# ODGIRON-v1_0-F4x1-0410.net
KiCad netlist of a schematic drawn in EAGLE
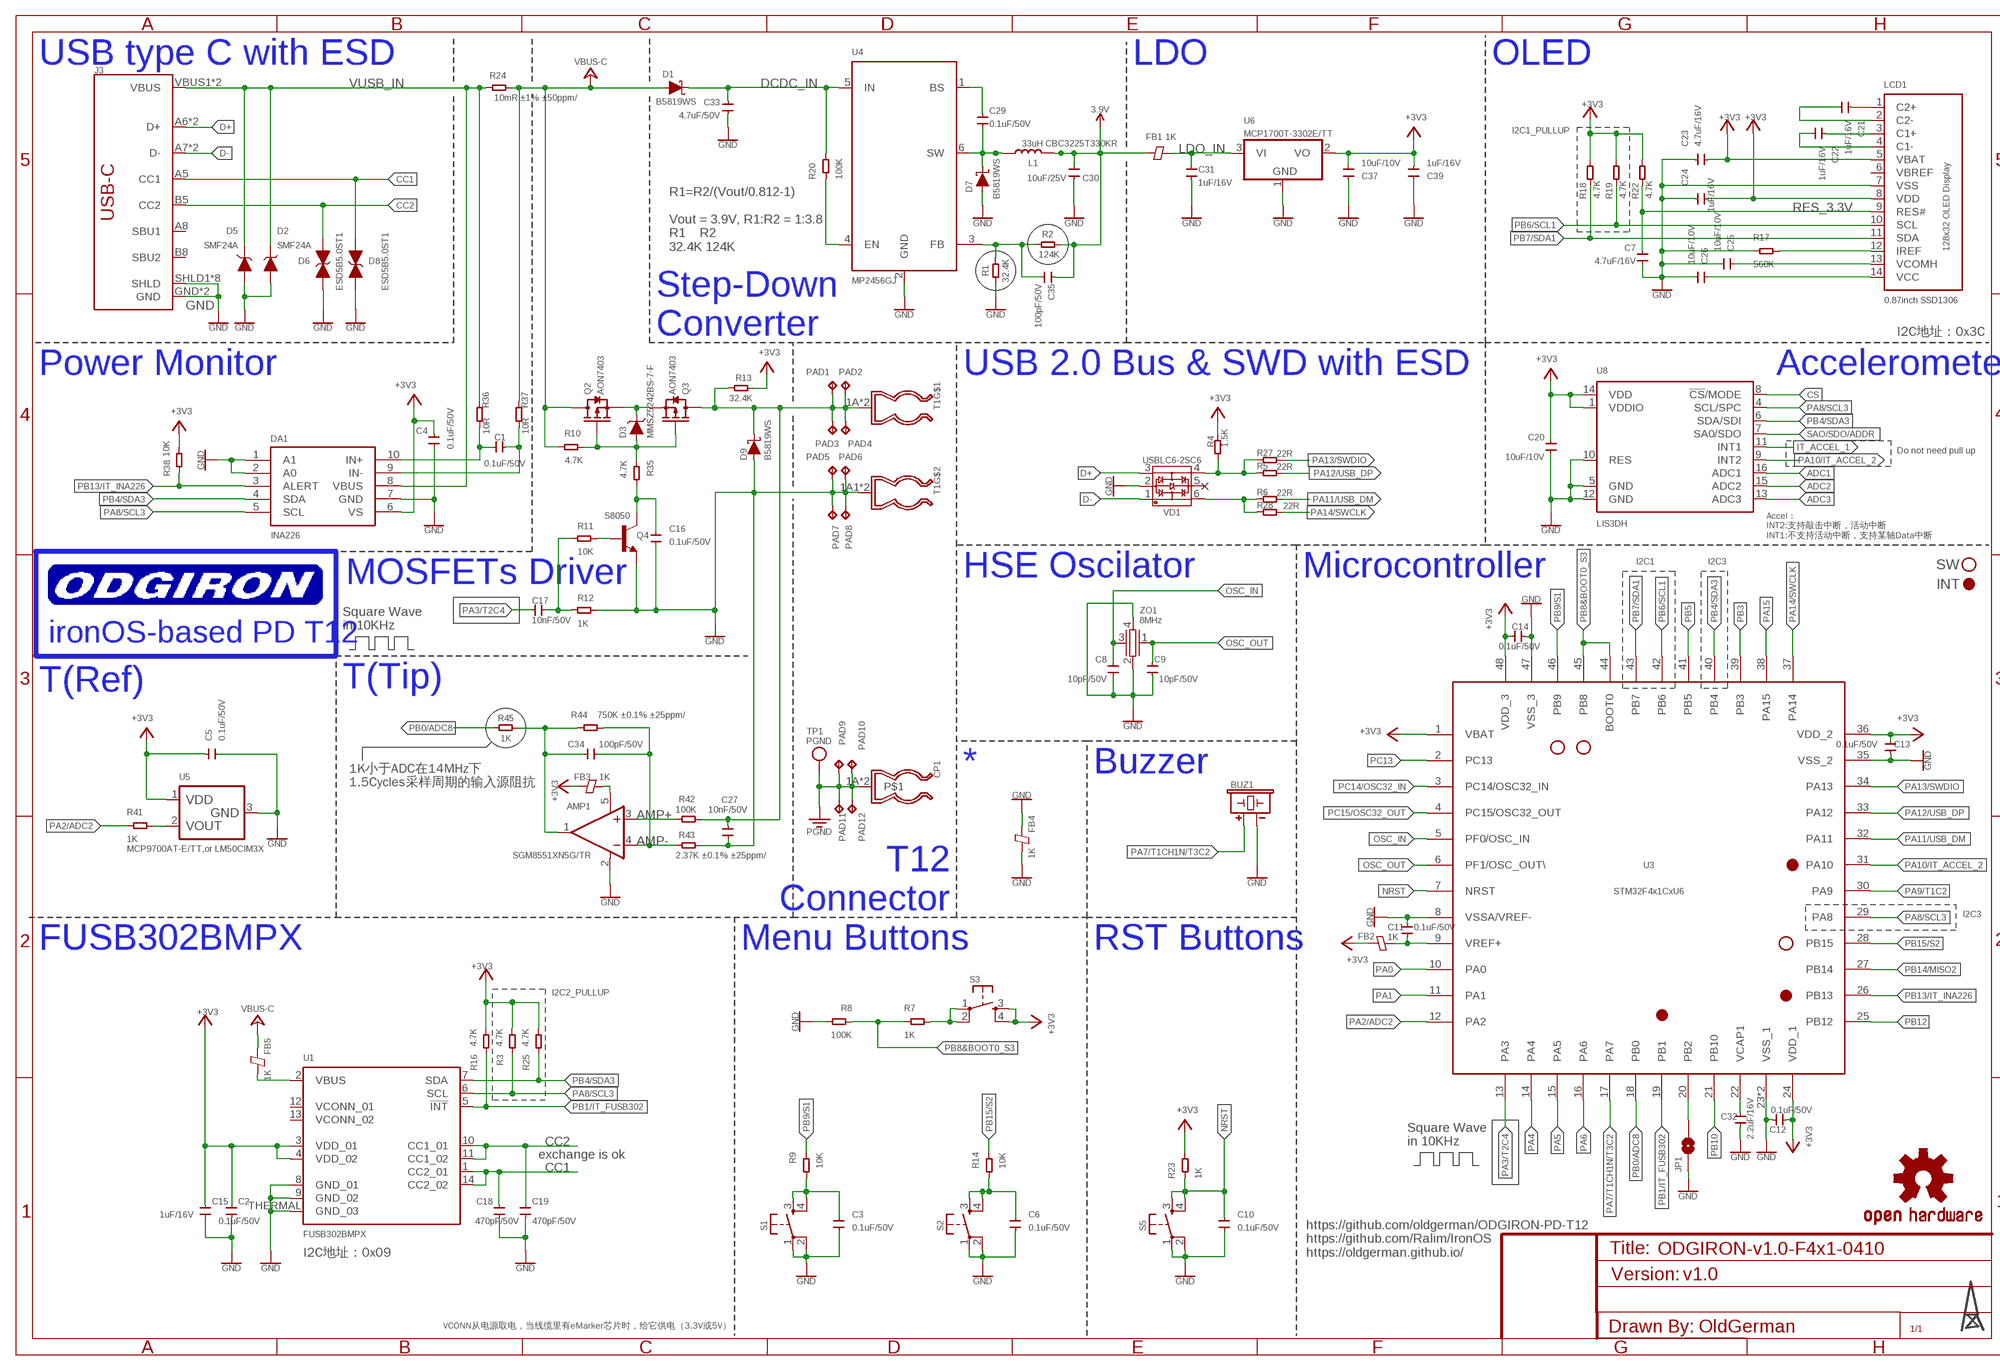
[diagram p0: schematic, sheet 1, part 1 of 2]
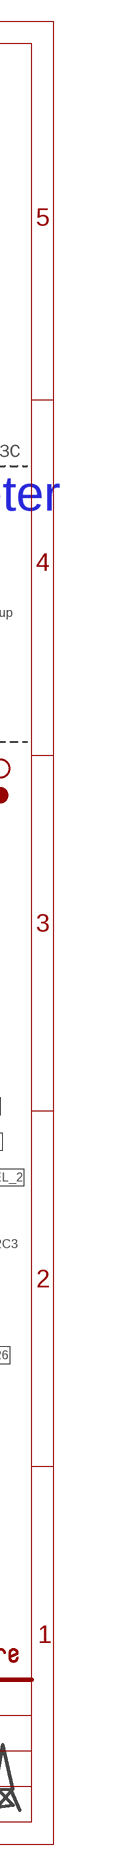
[diagram p1: schematic, sheet 1, part 2 of 2]

(export (version "E")
  (design (tool "Eeschema 10.0.6"))
  (components
    (comp (ref "AMP1")
      (value "SGM8551XN5G/TR")
      (footprint "eagle-import:SOT23-5")
      (fields (field (name "MPN") "OPA340NA/3KG4"))
      (libsource (lib "eagle-import") (part "AMP_SIMGLEN"))
    )
    (comp (ref "BUZ1")
      (value "BUZZERBUZZER_5020")
      (footprint "eagle-import:BUZZER_5020")
      (libsource (lib "eagle-import") (part "BUZZERBUZZER_5020"))
    )
    (comp (ref "C1")
      (value "0.1uF/50V")
      (footprint "eagle-import:C0603")
      (libsource (lib "eagle-import") (part "SEEED_CAP-0603"))
    )
    (comp (ref "C2")
      (value "0.1uF/50V")
      (footprint "eagle-import:C0603")
      (libsource (lib "eagle-import") (part "SEEED_CAP-0603"))
    )
    (comp (ref "C3")
      (value "0.1uF/50V")
      (footprint "eagle-import:C0603")
      (libsource (lib "eagle-import") (part "SEEED_CAP-0603"))
    )
    (comp (ref "C4")
      (value "0.1uF/50V")
      (footprint "eagle-import:C0603")
      (libsource (lib "eagle-import") (part "SEEED_CAP-0603"))
    )
    (comp (ref "C5")
      (value "0.1uF/50V")
      (footprint "eagle-import:C0603")
      (libsource (lib "eagle-import") (part "SEEED_CAP-0603"))
    )
    (comp (ref "C6")
      (value "0.1uF/50V")
      (footprint "eagle-import:C0603")
      (libsource (lib "eagle-import") (part "SEEED_CAP-0603"))
    )
    (comp (ref "C7")
      (value "4.7uF/16V")
      (footprint "eagle-import:C0603")
      (libsource (lib "eagle-import") (part "SEEED_CAP-0603"))
    )
    (comp (ref "C8")
      (value "10pF/50V")
      (footprint "eagle-import:C0603")
      (libsource (lib "eagle-import") (part "SEEED_CAP-0603"))
    )
    (comp (ref "C9")
      (value "10pF/50V")
      (footprint "eagle-import:C0603")
      (libsource (lib "eagle-import") (part "SEEED_CAP-0603"))
    )
    (comp (ref "C10")
      (value "0.1uF/50V")
      (footprint "eagle-import:C0603")
      (libsource (lib "eagle-import") (part "SEEED_CAP-0603"))
    )
    (comp (ref "C11")
      (value "0.1uF/50V")
      (footprint "eagle-import:C0603")
      (libsource (lib "eagle-import") (part "SEEED_CAP-0603"))
    )
    (comp (ref "C12")
      (value "0.1uF/50V")
      (footprint "eagle-import:C0603")
      (libsource (lib "eagle-import") (part "SEEED_CAP-0603"))
    )
    (comp (ref "C13")
      (value "0.1uF/50V")
      (footprint "eagle-import:C0603")
      (libsource (lib "eagle-import") (part "SEEED_CAP-0603"))
    )
    (comp (ref "C14")
      (value "0.1uF/50V")
      (footprint "eagle-import:C0603")
      (libsource (lib "eagle-import") (part "SEEED_CAP-0603"))
    )
    (comp (ref "C15")
      (value "1uF/16V")
      (footprint "eagle-import:C0603")
      (libsource (lib "eagle-import") (part "SEEED_CAP-0603"))
    )
    (comp (ref "C16")
      (value "0.1uF/50V")
      (footprint "eagle-import:C0603")
      (libsource (lib "eagle-import") (part "SEEED_CAP-0603"))
    )
    (comp (ref "C17")
      (value "10nF/50V")
      (footprint "eagle-import:C0603")
      (libsource (lib "eagle-import") (part "SEEED_CAP-0603"))
    )
    (comp (ref "C18")
      (value "470pF/50V")
      (footprint "eagle-import:C0603")
      (libsource (lib "eagle-import") (part "SEEED_CAP-0603"))
    )
    (comp (ref "C19")
      (value "470pF/50V")
      (footprint "eagle-import:C0603")
      (libsource (lib "eagle-import") (part "SEEED_CAP-0603"))
    )
    (comp (ref "C20")
      (value "10uF/10V")
      (footprint "eagle-import:C0603")
      (libsource (lib "eagle-import") (part "SEEED_CAP-0603"))
    )
    (comp (ref "C21")
      (value "1uF/16V")
      (footprint "eagle-import:C0603")
      (libsource (lib "eagle-import") (part "SEEED_CAP-0603"))
    )
    (comp (ref "C22")
      (value "1uF/16V")
      (footprint "eagle-import:C0603")
      (libsource (lib "eagle-import") (part "SEEED_CAP-0603"))
    )
    (comp (ref "C23")
      (value "4.7uF/16V")
      (footprint "eagle-import:C0603")
      (libsource (lib "eagle-import") (part "SEEED_CAP-0603"))
    )
    (comp (ref "C24")
      (value "1uF/16V")
      (footprint "eagle-import:C0603")
      (libsource (lib "eagle-import") (part "SEEED_CAP-0603"))
    )
    (comp (ref "C25")
      (value "10uF/10V")
      (footprint "eagle-import:C0603")
      (libsource (lib "eagle-import") (part "SEEED_CAP-0603"))
    )
    (comp (ref "C26")
      (value "10uF/10V")
      (footprint "eagle-import:C0603")
      (libsource (lib "eagle-import") (part "SEEED_CAP-0603"))
    )
    (comp (ref "C27")
      (value "10nF/50V")
      (footprint "eagle-import:C0603")
      (libsource (lib "eagle-import") (part "SEEED_CAP-0603"))
    )
    (comp (ref "C29")
      (value "0.1uF/50V")
      (footprint "eagle-import:C0603")
      (libsource (lib "eagle-import") (part "SEEED_CAP-0603"))
    )
    (comp (ref "C30")
      (value "10uF/25V")
      (footprint "eagle-import:C0805")
      (libsource (lib "eagle-import") (part "SEEED_CAP-0805"))
    )
    (comp (ref "C31")
      (value "1uF/16V")
      (footprint "eagle-import:C0603")
      (libsource (lib "eagle-import") (part "SEEED_CAP-0603"))
    )
    (comp (ref "C32")
      (value "2.2uF/16V")
      (footprint "eagle-import:C0603")
      (libsource (lib "eagle-import") (part "SEEED_CAP-0603"))
    )
    (comp (ref "C33")
      (value "4.7uF/50V")
      (footprint "eagle-import:C0805")
      (libsource (lib "eagle-import") (part "SEEED_CAP-0805"))
    )
    (comp (ref "C34")
      (value "100pF/50V")
      (footprint "eagle-import:C0603")
      (libsource (lib "eagle-import") (part "SEEED_CAP-0603"))
    )
    (comp (ref "C35")
      (value "100pF/50V")
      (footprint "eagle-import:C0603")
      (libsource (lib "eagle-import") (part "SEEED_CAP-0603"))
    )
    (comp (ref "C37")
      (value "10uF/10V")
      (footprint "eagle-import:C0603")
      (libsource (lib "eagle-import") (part "SEEED_CAP-0603"))
    )
    (comp (ref "C39")
      (value "1uF/16V")
      (footprint "eagle-import:C0603")
      (libsource (lib "eagle-import") (part "SEEED_CAP-0603"))
    )
    (comp (ref "CP1")
      (value "FUSE_CLIPS_01")
      (footprint "eagle-import:FUSE_CLIPS_01")
      (libsource (lib "eagle-import") (part "FUSE_CLIPS_01"))
    )
    (comp (ref "D1")
      (value "B5819WS")
      (footprint "eagle-import:SOD-323")
      (libsource (lib "eagle-import") (part "DIODE_SCHOTTKYSOD323"))
    )
    (comp (ref "D2")
      (value "SMF24A")
      (footprint "eagle-import:SOD-123")
      (libsource (lib "eagle-import") (part "DIODE-TVS_UNIDIRECTIONALSOD-123"))
    )
    (comp (ref "D3")
      (value "MMSZ5242BS-7-F")
      (footprint "eagle-import:SOD-323")
      (libsource (lib "eagle-import") (part "DIODE_ZENERSOD-323"))
    )
    (comp (ref "D5")
      (value "SMF24A")
      (footprint "eagle-import:SOD-123")
      (libsource (lib "eagle-import") (part "DIODE-TVS_UNIDIRECTIONALSOD-123"))
    )
    (comp (ref "D6")
      (value "ESD5B5.0ST1")
      (footprint "eagle-import:SOD-523")
      (libsource (lib "eagle-import") (part "DIODE-TVS_BI−DIRECTIONALSOD-523"))
    )
    (comp (ref "D7")
      (value "B5819WS")
      (footprint "eagle-import:SOD-323")
      (libsource (lib "eagle-import") (part "DIODE_SCHOTTKYSOD323"))
    )
    (comp (ref "D8")
      (value "ESD5B5.0ST1")
      (footprint "eagle-import:SOD-523")
      (libsource (lib "eagle-import") (part "DIODE-TVS_BI−DIRECTIONALSOD-523"))
    )
    (comp (ref "D9")
      (value "B5819WS")
      (footprint "eagle-import:SOD-323")
      (libsource (lib "eagle-import") (part "DIODE_SCHOTTKYSOD323"))
    )
    (comp (ref "DA1")
      (value "INA226")
      (footprint "eagle-import:MSOP10")
      (libsource (lib "eagle-import") (part "INA226"))
    )
    (comp (ref "FB1")
      (value "1K")
      (footprint "eagle-import:F0603")
      (libsource (lib "eagle-import") (part "FERRITE-BEAD-0603"))
    )
    (comp (ref "FB2")
      (value "1K")
      (footprint "eagle-import:F0603")
      (libsource (lib "eagle-import") (part "FERRITE-BEAD-0603"))
    )
    (comp (ref "FB3")
      (value "1K")
      (footprint "eagle-import:F0603")
      (libsource (lib "eagle-import") (part "FERRITE-BEAD-0603"))
    )
    (comp (ref "FB4")
      (value "1K")
      (footprint "eagle-import:F0603")
      (libsource (lib "eagle-import") (part "FERRITE-BEAD-0603"))
    )
    (comp (ref "FB5")
      (value "1K")
      (footprint "eagle-import:F0603")
      (libsource (lib "eagle-import") (part "FERRITE-BEAD-0603"))
    )
    (comp (ref "J3")
      (value "USB_C_LONG-SYMBOL2-LAYER")
      (footprint "eagle-import:USB-C-16P")
      (libsource (lib "eagle-import") (part "USB_C_LONG-SYMBOL2-LAYER"))
    )
    (comp (ref "JP1")
      (value "JUMPER-SMT_2_NO_SILK")
      (footprint "eagle-import:SMT-JUMPER_2_NO_SILK")
      (libsource (lib "eagle-import") (part "JUMPER-SMT_2_NO_SILK"))
    )
    (comp (ref "L1")
      (value "33uH CBC3225T330KR")
      (footprint "eagle-import:SMD,3.2X2.5X2.5MM")
      (libsource (lib "eagle-import") (part "INDUCTOR3225"))
    )
    (comp (ref "LCD1")
      (value "0.87inch SSD1306")
      (footprint "eagle-import:0.87INCH_128X32_OLED_SSD1306")
      (libsource (lib "eagle-import") (part "0.87INCH_OLED_128X32_SSD1306"))
    )
    (comp (ref "LOGO1")
      (value "OSHW-LOGONO_SILK")
      (footprint "eagle-import:DUMMY")
      (libsource (lib "eagle-import") (part "OSHW-LOGONO_SILK"))
    )
    (comp (ref "PAD1")
      (value "PADTP16SQ")
      (footprint "eagle-import:TP16SQ")
      (libsource (lib "eagle-import") (part "PADTP16SQ"))
    )
    (comp (ref "PAD2")
      (value "PADTP16SQ")
      (footprint "eagle-import:TP16SQ")
      (libsource (lib "eagle-import") (part "PADTP16SQ"))
    )
    (comp (ref "PAD3")
      (value "PADTP16SQ")
      (footprint "eagle-import:TP16SQ")
      (libsource (lib "eagle-import") (part "PADTP16SQ"))
    )
    (comp (ref "PAD4")
      (value "PADTP16SQ")
      (footprint "eagle-import:TP16SQ")
      (libsource (lib "eagle-import") (part "PADTP16SQ"))
    )
    (comp (ref "PAD5")
      (value "PADTP16SQ")
      (footprint "eagle-import:TP16SQ")
      (libsource (lib "eagle-import") (part "PADTP16SQ"))
    )
    (comp (ref "PAD6")
      (value "PADTP16SQ")
      (footprint "eagle-import:TP16SQ")
      (libsource (lib "eagle-import") (part "PADTP16SQ"))
    )
    (comp (ref "PAD7")
      (value "PADTP16SQ")
      (footprint "eagle-import:TP16SQ")
      (libsource (lib "eagle-import") (part "PADTP16SQ"))
    )
    (comp (ref "PAD8")
      (value "PADTP16SQ")
      (footprint "eagle-import:TP16SQ")
      (libsource (lib "eagle-import") (part "PADTP16SQ"))
    )
    (comp (ref "PAD9")
      (value "PADTP16SQ")
      (footprint "eagle-import:TP16SQ")
      (libsource (lib "eagle-import") (part "PADTP16SQ"))
    )
    (comp (ref "PAD10")
      (value "PADTP16SQ")
      (footprint "eagle-import:TP16SQ")
      (libsource (lib "eagle-import") (part "PADTP16SQ"))
    )
    (comp (ref "PAD11")
      (value "PADTP16SQ")
      (footprint "eagle-import:TP16SQ")
      (libsource (lib "eagle-import") (part "PADTP16SQ"))
    )
    (comp (ref "PAD12")
      (value "PADTP16SQ")
      (footprint "eagle-import:TP16SQ")
      (libsource (lib "eagle-import") (part "PADTP16SQ"))
    )
    (comp (ref "Q2")
      (value "AON7403")
      (footprint "eagle-import:DFN8P-0.65-3X3X0.8MM")
      (libsource (lib "eagle-import") (part "MOSFET-P-AON7403"))
    )
    (comp (ref "Q3")
      (value "AON7403")
      (footprint "eagle-import:DFN8P-0.65-3X3X0.8MM")
      (libsource (lib "eagle-import") (part "MOSFET-P-AON7403"))
    )
    (comp (ref "Q4")
      (value "S8050")
      (footprint "eagle-import:SOT23-3")
      (libsource (lib "eagle-import") (part "TRANS_NPN-MMBT2222AL"))
    )
    (comp (ref "R1")
      (value "32.4K")
      (footprint "eagle-import:R0603")
      (libsource (lib "eagle-import") (part "SEEED_RES-0603"))
    )
    (comp (ref "R2")
      (value "124K")
      (footprint "eagle-import:R0603")
      (libsource (lib "eagle-import") (part "SEEED_RES-0603"))
    )
    (comp (ref "R3")
      (value "4.7K")
      (footprint "eagle-import:R0603")
      (libsource (lib "eagle-import") (part "SEEED_RES-0603"))
    )
    (comp (ref "R4")
      (value "1.5K")
      (footprint "eagle-import:R0603")
      (libsource (lib "eagle-import") (part "SEEED_RES-0603"))
    )
    (comp (ref "R5")
      (value "22R")
      (footprint "eagle-import:R0603")
      (libsource (lib "eagle-import") (part "SEEED_RES-0603"))
    )
    (comp (ref "R6")
      (value "22R")
      (footprint "eagle-import:R0603")
      (libsource (lib "eagle-import") (part "SEEED_RES-0603"))
    )
    (comp (ref "R7")
      (value "1K")
      (footprint "eagle-import:R0603")
      (libsource (lib "eagle-import") (part "SEEED_RES-0603"))
    )
    (comp (ref "R8")
      (value "100K")
      (footprint "eagle-import:R0603")
      (libsource (lib "eagle-import") (part "SEEED_RES-0603"))
    )
    (comp (ref "R9")
      (value "10K")
      (footprint "eagle-import:R0603")
      (libsource (lib "eagle-import") (part "SEEED_RES-0603"))
    )
    (comp (ref "R10")
      (value "4.7K")
      (footprint "eagle-import:R0603")
      (libsource (lib "eagle-import") (part "SEEED_RES-0603"))
    )
    (comp (ref "R11")
      (value "10K")
      (footprint "eagle-import:R0603")
      (libsource (lib "eagle-import") (part "SEEED_RES-0603"))
    )
    (comp (ref "R12")
      (value "1K")
      (footprint "eagle-import:R0603")
      (libsource (lib "eagle-import") (part "SEEED_RES-0603"))
    )
    (comp (ref "R13")
      (value "32.4K")
      (footprint "eagle-import:R0603")
      (libsource (lib "eagle-import") (part "SEEED_RES-0603"))
    )
    (comp (ref "R14")
      (value "10K")
      (footprint "eagle-import:R0603")
      (libsource (lib "eagle-import") (part "SEEED_RES-0603"))
    )
    (comp (ref "R16")
      (value "4.7K")
      (footprint "eagle-import:R0603")
      (libsource (lib "eagle-import") (part "SEEED_RES-0603"))
    )
    (comp (ref "R17")
      (value "560K")
      (footprint "eagle-import:R0603")
      (libsource (lib "eagle-import") (part "SEEED_RES-0603"))
    )
    (comp (ref "R18")
      (value "4.7K")
      (footprint "eagle-import:R0603")
      (libsource (lib "eagle-import") (part "SEEED_RES-0603"))
    )
    (comp (ref "R19")
      (value "4.7K")
      (footprint "eagle-import:R0603")
      (libsource (lib "eagle-import") (part "SEEED_RES-0603"))
    )
    (comp (ref "R20")
      (value "100K")
      (footprint "eagle-import:R0603")
      (libsource (lib "eagle-import") (part "SEEED_RES-0603"))
    )
    (comp (ref "R22")
      (value "4.7K")
      (footprint "eagle-import:R0603")
      (libsource (lib "eagle-import") (part "SEEED_RES-0603"))
    )
    (comp (ref "R23")
      (value "1K")
      (footprint "eagle-import:R0603")
      (libsource (lib "eagle-import") (part "SEEED_RES-0603"))
    )
    (comp (ref "R24")
      (value "10mR ±1% ±50ppm/℃")
      (footprint "eagle-import:R1206")
      (libsource (lib "eagle-import") (part "SEEED_RES-1206"))
    )
    (comp (ref "R25")
      (value "4.7K")
      (footprint "eagle-import:R0603")
      (libsource (lib "eagle-import") (part "SEEED_RES-0603"))
    )
    (comp (ref "R27")
      (value "22R")
      (footprint "eagle-import:R0603")
      (libsource (lib "eagle-import") (part "SEEED_RES-0603"))
    )
    (comp (ref "R28")
      (value "22R")
      (footprint "eagle-import:R0603")
      (libsource (lib "eagle-import") (part "SEEED_RES-0603"))
    )
    (comp (ref "R35")
      (value "4.7K")
      (footprint "eagle-import:R0603")
      (libsource (lib "eagle-import") (part "SEEED_RES-0603"))
    )
    (comp (ref "R36")
      (value "10R")
      (footprint "eagle-import:R0603")
      (libsource (lib "eagle-import") (part "SEEED_RES-0603"))
    )
    (comp (ref "R37")
      (value "10R")
      (footprint "eagle-import:R0603")
      (libsource (lib "eagle-import") (part "SEEED_RES-0603"))
    )
    (comp (ref "R38")
      (value "10K")
      (footprint "eagle-import:R0603")
      (libsource (lib "eagle-import") (part "SEEED_RES-0603"))
    )
    (comp (ref "R41")
      (value "1K")
      (footprint "eagle-import:R0603")
      (libsource (lib "eagle-import") (part "SEEED_RES-0603"))
    )
    (comp (ref "R42")
      (value "100K")
      (footprint "eagle-import:R0603")
      (libsource (lib "eagle-import") (part "SEEED_RES-0603"))
    )
    (comp (ref "R43")
      (value "2.37K ±0.1% ±25ppm/℃")
      (footprint "eagle-import:R0603")
      (libsource (lib "eagle-import") (part "SEEED_RES-0603"))
    )
    (comp (ref "R44")
      (value "750K ±0.1% ±25ppm/℃")
      (footprint "eagle-import:R0603")
      (libsource (lib "eagle-import") (part "SEEED_RES-0603"))
    )
    (comp (ref "R45")
      (value "1K")
      (footprint "eagle-import:R0603")
      (libsource (lib "eagle-import") (part "SEEED_RES-0603"))
    )
    (comp (ref "S1")
      (value "TAC_SWITCHSMD")
      (footprint "eagle-import:TACTILE_SWITCH_SMD")
      (libsource (lib "eagle-import") (part "TAC_SWITCHSMD"))
    )
    (comp (ref "S2")
      (value "TAC_SWITCHSMD")
      (footprint "eagle-import:TACTILE_SWITCH_SMD")
      (libsource (lib "eagle-import") (part "TAC_SWITCHSMD"))
    )
    (comp (ref "S3")
      (value "TAC_SWITCHSMD")
      (footprint "eagle-import:TACTILE_SWITCH_SMD")
      (libsource (lib "eagle-import") (part "TAC_SWITCHSMD"))
    )
    (comp (ref "S5")
      (value "TAC_SWITCHSMD")
      (footprint "eagle-import:TACTILE_SWITCH_SMD")
      (libsource (lib "eagle-import") (part "untitled_TAC_SWITCHSMD"))
    )
    (comp (ref "T1")
      (value "HAKKO_T12_K-TYPE_WITH_FUSE_CLIPS_X2")
      (footprint "eagle-import:HAKKO_T12_K-TYPE_WITH_FUSE_CLIPS_X2")
      (libsource (lib "eagle-import") (part "HAKKO_T12_K-TYPE_WITH_FUSE_CLIPS_X2"))
    )
    (comp (ref "TP1")
      (value "PGND")
      (footprint "eagle-import:TESTPOINT_ROUND_2MM")
      (libsource (lib "eagle-import") (part "TESTPOINTROUND2MM"))
    )
    (comp (ref "U1")
      (value "FUSB302BMPX")
      (footprint "eagle-import:QFN14-2.5X2.5MM")
      (libsource (lib "eagle-import") (part "FUSB302"))
    )
    (comp (ref "U3")
      (value "STM32F4x1CxU6")
      (footprint "eagle-import:QFN48_7X7MM_0.5MM")
      (libsource (lib "eagle-import") (part "STM32F4_QFN48"))
    )
    (comp (ref "U4")
      (value "MP2456GJ")
      (footprint "eagle-import:SOT23-6")
      (libsource (lib "eagle-import") (part "MP2456"))
    )
    (comp (ref "U5")
      (value "MCP9700AT-E/TT,or LM50CIM3X")
      (footprint "eagle-import:SOT23-3@1")
      (libsource (lib "eagle-import") (part "MCP9700"))
    )
    (comp (ref "U6")
      (value "MCP1700T-3302E/TT")
      (footprint "eagle-import:SOT23-3")
      (libsource (lib "eagle-import") (part "MCP1700"))
    )
    (comp (ref "U8")
      (value "LIS3DH")
      (footprint "eagle-import:LGA-16-3X3")
      (libsource (lib "eagle-import") (part "LIS3DH"))
    )
    (comp (ref "VD1")
      (value "USBLC6-2SC6")
      (footprint "eagle-import:SOT23-6")
      (libsource (lib "eagle-import") (part "USBLC6-2SOT23-6"))
    )
    (comp (ref "ZO1")
      (value "8MHz")
      (footprint "eagle-import:3.2X2.5_KX-7")
      (libsource (lib "eagle-import") (part "3225_CRYSTALL"))
    )
  )
  (nets
    (net (code "1") (name "+3V3") (class "Default")
      (node (ref "C12") (pin "2") (pinfunction "P$2_2") (pintype "passive"))
      (node (ref "C13") (pin "2") (pinfunction "P$2_2") (pintype "passive"))
      (node (ref "C14") (pin "2") (pinfunction "P$2_2") (pintype "passive"))
      (node (ref "C15") (pin "1") (pinfunction "P$1_1") (pintype "passive"))
      (node (ref "C2") (pin "1") (pinfunction "P$1_1") (pintype "passive"))
      (node (ref "C20") (pin "2") (pinfunction "P$2_2") (pintype "passive"))
      (node (ref "C23") (pin "2") (pinfunction "P$2_2") (pintype "passive"))
      (node (ref "C24") (pin "2") (pinfunction "P$2_2") (pintype "passive"))
      (node (ref "C37") (pin "2") (pinfunction "P$2_2") (pintype "passive"))
      (node (ref "C39") (pin "2") (pinfunction "P$2_2") (pintype "passive"))
      (node (ref "C4") (pin "1") (pinfunction "P$1_1") (pintype "passive"))
      (node (ref "C5") (pin "1") (pinfunction "P$1_1") (pintype "passive"))
      (node (ref "DA1") (pin "6") (pinfunction "VS_6") (pintype "bidirectional"))
      (node (ref "FB2") (pin "2") (pinfunction "2_2") (pintype "bidirectional"))
      (node (ref "FB3") (pin "2") (pinfunction "2_2") (pintype "bidirectional"))
      (node (ref "LCD1") (pin "5") (pinfunction "VBAT_5") (pintype "power_in"))
      (node (ref "LCD1") (pin "8") (pinfunction "VDD_8") (pintype "power_in"))
      (node (ref "R13") (pin "2") (pinfunction "2_2") (pintype "passive"))
      (node (ref "R16") (pin "1") (pinfunction "1_1") (pintype "passive"))
      (node (ref "R18") (pin "2") (pinfunction "2_2") (pintype "passive"))
      (node (ref "R19") (pin "2") (pinfunction "2_2") (pintype "passive"))
      (node (ref "R22") (pin "2") (pinfunction "2_2") (pintype "passive"))
      (node (ref "R23") (pin "2") (pinfunction "2_2") (pintype "passive"))
      (node (ref "R25") (pin "1") (pinfunction "1_1") (pintype "passive"))
      (node (ref "R3") (pin "1") (pinfunction "1_1") (pintype "passive"))
      (node (ref "R38") (pin "1") (pinfunction "1_1") (pintype "passive"))
      (node (ref "R4") (pin "2") (pinfunction "2_2") (pintype "passive"))
      (node (ref "S3") (pin "3") (pinfunction "3_3") (pintype "passive"))
      (node (ref "S3") (pin "4") (pinfunction "4_4") (pintype "passive"))
      (node (ref "U1") (pin "3") (pinfunction "VDD_01_3") (pintype "bidirectional"))
      (node (ref "U1") (pin "4") (pinfunction "VDD_02_4") (pintype "bidirectional"))
      (node (ref "U3") (pin "1") (pinfunction "VBAT_1") (pintype "bidirectional"))
      (node (ref "U3") (pin "24") (pinfunction "VDD_1_24") (pintype "bidirectional"))
      (node (ref "U3") (pin "36") (pinfunction "VDD_2_36") (pintype "bidirectional"))
      (node (ref "U3") (pin "48") (pinfunction "VDD_3_48") (pintype "bidirectional"))
      (node (ref "U5") (pin "1") (pinfunction "VDD_1") (pintype "input"))
      (node (ref "U6") (pin "2") (pinfunction "VO_2") (pintype "passive"))
      (node (ref "U8") (pin "1") (pinfunction "VDDIO_1") (pintype "bidirectional"))
      (node (ref "U8") (pin "14") (pinfunction "VDD_14") (pintype "bidirectional"))
    )
    (net (code "2") (name "/AMP+") (class "Default")
      (node (ref "AMP1") (pin "3") (pinfunction "+IN_3") (pintype "input"))
      (node (ref "R42") (pin "1") (pinfunction "1_1") (pintype "passive"))
    )
    (net (code "3") (name "/AMP-") (class "Default")
      (node (ref "AMP1") (pin "4") (pinfunction "-IN_4") (pintype "input"))
      (node (ref "C34") (pin "2") (pinfunction "P$2_2") (pintype "passive"))
      (node (ref "R43") (pin "1") (pinfunction "1_1") (pintype "passive"))
      (node (ref "R44") (pin "2") (pinfunction "2_2") (pintype "passive"))
    )
    (net (code "4") (name "/DCDC_IN") (class "Default")
      (node (ref "C33") (pin "1") (pinfunction "P$1_1") (pintype "passive"))
      (node (ref "D1") (pin "C") (pinfunction "C_C") (pintype "passive"))
      (node (ref "R20") (pin "2") (pinfunction "2_2") (pintype "passive"))
      (node (ref "U4") (pin "5") (pinfunction "IN_5") (pintype "bidirectional"))
    )
    (net (code "5") (name "/LDO_IN") (class "Default")
      (node (ref "C31") (pin "2") (pinfunction "P$2_2") (pintype "passive"))
      (node (ref "FB1") (pin "2") (pinfunction "2_2") (pintype "bidirectional"))
      (node (ref "U6") (pin "3") (pinfunction "VI_3") (pintype "input"))
    )
    (net (code "6") (name "/RES_3.3V") (class "Default")
      (node (ref "C7") (pin "1") (pinfunction "P$1_1") (pintype "passive"))
      (node (ref "LCD1") (pin "9") (pinfunction "RES#_9") (pintype "bidirectional"))
      (node (ref "R22") (pin "1") (pinfunction "1_1") (pintype "passive"))
    )
    (net (code "7") (name "/VBREF") (class "Default")
      (node (ref "LCD1") (pin "6") (pinfunction "VBREF_6") (pintype "power_in"))
    )
    (net (code "8") (name "/VUSB_IN") (class "Default")
      (node (ref "D2") (pin "C") (pinfunction "K_C") (pintype "passive"))
      (node (ref "D5") (pin "C") (pinfunction "K_C") (pintype "passive"))
      (node (ref "DA1") (pin "8") (pinfunction "VBUS_8") (pintype "bidirectional"))
      (node (ref "J3") (pin "VBUS1") (pinfunction "VBUS_VBUS1") (pintype "bidirectional"))
      (node (ref "J3") (pin "VBUS2") (pinfunction "VBUS_VBUS2") (pintype "bidirectional"))
      (node (ref "R24") (pin "2") (pinfunction "2_2") (pintype "passive"))
      (node (ref "R36") (pin "2") (pinfunction "2_2") (pintype "passive"))
    )
    (net (code "9") (name "3.9V") (class "Default")
      (node (ref "C30") (pin "1") (pinfunction "P$1_1") (pintype "passive"))
      (node (ref "C35") (pin "1") (pinfunction "P$1_1") (pintype "passive"))
      (node (ref "FB1") (pin "1") (pinfunction "1_1") (pintype "bidirectional"))
      (node (ref "L1") (pin "2") (pinfunction "2_2") (pintype "passive"))
      (node (ref "R2") (pin "1") (pinfunction "1_1") (pintype "passive"))
    )
    (net (code "10") (name "ADC1") (class "Default")
      (node (ref "U8") (pin "16") (pinfunction "ADC1_16") (pintype "bidirectional"))
    )
    (net (code "11") (name "ADC2") (class "Default")
      (node (ref "U8") (pin "15") (pinfunction "ADC2_15") (pintype "bidirectional"))
    )
    (net (code "12") (name "ADC3") (class "Default")
      (node (ref "U8") (pin "13") (pinfunction "ADC3_13") (pintype "bidirectional"))
    )
    (net (code "13") (name "CC1") (class "Default")
      (node (ref "C18") (pin "1") (pinfunction "P$1_1") (pintype "passive"))
      (node (ref "D8") (pin "K") (pinfunction "C_K") (pintype "passive"))
      (node (ref "J3") (pin "A5") (pinfunction "CC1_A5") (pintype "bidirectional"))
      (node (ref "U1") (pin "1") (pinfunction "CC2_01_1") (pintype "bidirectional"))
      (node (ref "U1") (pin "14") (pinfunction "CC2_02_14") (pintype "bidirectional"))
    )
    (net (code "14") (name "CC2") (class "Default")
      (node (ref "C19") (pin "1") (pinfunction "P$1_1") (pintype "passive"))
      (node (ref "D6") (pin "K") (pinfunction "C_K") (pintype "passive"))
      (node (ref "J3") (pin "B5") (pinfunction "CC2_B5") (pintype "bidirectional"))
      (node (ref "U1") (pin "10") (pinfunction "CC1_01_10") (pintype "bidirectional"))
      (node (ref "U1") (pin "11") (pinfunction "CC1_02_11") (pintype "bidirectional"))
    )
    (net (code "15") (name "CS") (class "Default")
      (node (ref "U8") (pin "8") (pinfunction "~{CS}/MODE_8") (pintype "bidirectional"))
    )
    (net (code "16") (name "D+") (class "Default")
      (node (ref "J3") (pin "A6") (pinfunction "D+_A6") (pintype "bidirectional"))
      (node (ref "J3") (pin "B6") (pinfunction "D+_B6") (pintype "bidirectional"))
      (node (ref "VD1") (pin "3") (pinfunction "P$3_3") (pintype "bidirectional"))
    )
    (net (code "17") (name "D-") (class "Default")
      (node (ref "J3") (pin "A7") (pinfunction "D-_A7") (pintype "bidirectional"))
      (node (ref "J3") (pin "B7") (pinfunction "D-_B7") (pintype "bidirectional"))
      (node (ref "VD1") (pin "1") (pinfunction "P$1_1") (pintype "bidirectional"))
    )
    (net (code "18") (name "GND") (class "Default")
      (node (ref "AMP1") (pin "2") (pinfunction "V-_2") (pintype "power_in"))
      (node (ref "BUZ1") (pin "-") (pinfunction "LEAD-_-") (pintype "passive"))
      (node (ref "C10") (pin "2") (pinfunction "P$2_2") (pintype "passive"))
      (node (ref "C11") (pin "1") (pinfunction "P$1_1") (pintype "passive"))
      (node (ref "C12") (pin "1") (pinfunction "P$1_1") (pintype "passive"))
      (node (ref "C13") (pin "1") (pinfunction "P$1_1") (pintype "passive"))
      (node (ref "C14") (pin "1") (pinfunction "P$1_1") (pintype "passive"))
      (node (ref "C15") (pin "2") (pinfunction "P$2_2") (pintype "passive"))
      (node (ref "C16") (pin "1") (pinfunction "P$1_1") (pintype "passive"))
      (node (ref "C18") (pin "2") (pinfunction "P$2_2") (pintype "passive"))
      (node (ref "C19") (pin "2") (pinfunction "P$2_2") (pintype "passive"))
      (node (ref "C2") (pin "2") (pinfunction "P$2_2") (pintype "passive"))
      (node (ref "C20") (pin "1") (pinfunction "P$1_1") (pintype "passive"))
      (node (ref "C23") (pin "1") (pinfunction "P$1_1") (pintype "passive"))
      (node (ref "C24") (pin "1") (pinfunction "P$1_1") (pintype "passive"))
      (node (ref "C25") (pin "2") (pinfunction "P$2_2") (pintype "passive"))
      (node (ref "C26") (pin "2") (pinfunction "P$2_2") (pintype "passive"))
      (node (ref "C27") (pin "2") (pinfunction "P$2_2") (pintype "passive"))
      (node (ref "C3") (pin "2") (pinfunction "P$2_2") (pintype "passive"))
      (node (ref "C30") (pin "2") (pinfunction "P$2_2") (pintype "passive"))
      (node (ref "C31") (pin "1") (pinfunction "P$1_1") (pintype "passive"))
      (node (ref "C32") (pin "2") (pinfunction "P$2_2") (pintype "passive"))
      (node (ref "C33") (pin "2") (pinfunction "P$2_2") (pintype "passive"))
      (node (ref "C37") (pin "1") (pinfunction "P$1_1") (pintype "passive"))
      (node (ref "C39") (pin "1") (pinfunction "P$1_1") (pintype "passive"))
      (node (ref "C4") (pin "2") (pinfunction "P$2_2") (pintype "passive"))
      (node (ref "C5") (pin "2") (pinfunction "P$2_2") (pintype "passive"))
      (node (ref "C6") (pin "2") (pinfunction "P$2_2") (pintype "passive"))
      (node (ref "C7") (pin "2") (pinfunction "P$2_2") (pintype "passive"))
      (node (ref "C8") (pin "1") (pinfunction "P$1_1") (pintype "passive"))
      (node (ref "C9") (pin "1") (pinfunction "P$1_1") (pintype "passive"))
      (node (ref "D2") (pin "A") (pinfunction "A_A") (pintype "passive"))
      (node (ref "D5") (pin "A") (pinfunction "A_A") (pintype "passive"))
      (node (ref "D6") (pin "A") (pinfunction "A_A") (pintype "passive"))
      (node (ref "D7") (pin "A") (pinfunction "A_A") (pintype "passive"))
      (node (ref "D8") (pin "A") (pinfunction "A_A") (pintype "passive"))
      (node (ref "D9") (pin "A") (pinfunction "A_A") (pintype "passive"))
      (node (ref "DA1") (pin "1") (pinfunction "A1_1") (pintype "bidirectional"))
      (node (ref "DA1") (pin "2") (pinfunction "A0_2") (pintype "bidirectional"))
      (node (ref "DA1") (pin "7") (pinfunction "GND_7") (pintype "bidirectional"))
      (node (ref "FB4") (pin "1") (pinfunction "1_1") (pintype "bidirectional"))
      (node (ref "FB4") (pin "2") (pinfunction "2_2") (pintype "bidirectional"))
      (node (ref "J3") (pin "GND") (pinfunction "GND_GND") (pintype "bidirectional"))
      (node (ref "J3") (pin "GND2") (pinfunction "GND_GND2") (pintype "bidirectional"))
      (node (ref "J3") (pin "SHLD1") (pinfunction "SHLD_SHLD1") (pintype "bidirectional"))
      (node (ref "J3") (pin "SHLD2") (pinfunction "SHLD_SHLD2") (pintype "bidirectional"))
      (node (ref "J3") (pin "SHLD3") (pinfunction "SHLD_SHLD3") (pintype "bidirectional"))
      (node (ref "J3") (pin "SHLD4") (pinfunction "SHLD_SHLD4") (pintype "bidirectional"))
      (node (ref "J3") (pin "SHLD5") (pinfunction "SHLD_SHLD5") (pintype "bidirectional"))
      (node (ref "J3") (pin "SHLD6") (pinfunction "SHLD_SHLD6") (pintype "bidirectional"))
      (node (ref "J3") (pin "SHLD7") (pinfunction "SHLD_SHLD7") (pintype "bidirectional"))
      (node (ref "J3") (pin "SHLD8") (pinfunction "SHLD_SHLD8") (pintype "bidirectional"))
      (node (ref "JP1") (pin "1") (pinfunction "1_1") (pintype "passive"))
      (node (ref "LCD1") (pin "7") (pinfunction "VSS_7") (pintype "power_in"))
      (node (ref "PAD5") (pin "TP") (pinfunction "TP_TP") (pintype "input"))
      (node (ref "PAD6") (pin "TP") (pinfunction "TP_TP") (pintype "input"))
      (node (ref "PAD7") (pin "TP") (pinfunction "TP_TP") (pintype "input"))
      (node (ref "PAD8") (pin "TP") (pinfunction "TP_TP") (pintype "input"))
      (node (ref "Q4") (pin "2") (pinfunction "E_2") (pintype "passive"))
      (node (ref "R1") (pin "1") (pinfunction "1_1") (pintype "passive"))
      (node (ref "R12") (pin "1") (pinfunction "1_1") (pintype "passive"))
      (node (ref "R17") (pin "1") (pinfunction "1_1") (pintype "passive"))
      (node (ref "R43") (pin "2") (pinfunction "2_2") (pintype "passive"))
      (node (ref "R8") (pin "2") (pinfunction "2_2") (pintype "passive"))
      (node (ref "S1") (pin "1") (pinfunction "1_1") (pintype "passive"))
      (node (ref "S1") (pin "2") (pinfunction "2_2") (pintype "passive"))
      (node (ref "S2") (pin "1") (pinfunction "1_1") (pintype "passive"))
      (node (ref "S2") (pin "2") (pinfunction "2_2") (pintype "passive"))
      (node (ref "S5") (pin "1") (pinfunction "1_1") (pintype "passive"))
      (node (ref "S5") (pin "2") (pinfunction "2_2") (pintype "passive"))
      (node (ref "T1") (pin "1A1") (pinfunction "P$1_1A1") (pintype "bidirectional"))
      (node (ref "T1") (pin "1B1") (pinfunction "P$1_1B1") (pintype "bidirectional"))
      (node (ref "U1") (pin "8") (pinfunction "GND_01_8") (pintype "bidirectional"))
      (node (ref "U1") (pin "9") (pinfunction "GND_02_9") (pintype "bidirectional"))
      (node (ref "U1") (pin "THERMAL") (pinfunction "GND_03_THERMAL") (pintype "bidirectional"))
      (node (ref "U3") (pin "23") (pinfunction "VSS_1_23") (pintype "bidirectional"))
      (node (ref "U3") (pin "35") (pinfunction "VSS_2_35") (pintype "bidirectional"))
      (node (ref "U3") (pin "47") (pinfunction "VSS_3_47") (pintype "bidirectional"))
      (node (ref "U3") (pin "8") (pinfunction "VSSA/VREF-_8") (pintype "bidirectional"))
      (node (ref "U3") (pin "P$1") (pinfunction "VSS_1_P$1") (pintype "bidirectional"))
      (node (ref "U4") (pin "2") (pinfunction "GND_2") (pintype "bidirectional"))
      (node (ref "U5") (pin "3") (pinfunction "GND_3") (pintype "passive"))
      (node (ref "U6") (pin "1") (pinfunction "GND_1") (pintype "passive"))
      (node (ref "U8") (pin "10") (pinfunction "RES_10") (pintype "bidirectional"))
      (node (ref "U8") (pin "12") (pinfunction "GND_12") (pintype "bidirectional"))
      (node (ref "U8") (pin "5") (pinfunction "GND_5") (pintype "bidirectional"))
      (node (ref "VD1") (pin "2") (pinfunction "P$2_2") (pintype "bidirectional"))
      (node (ref "ZO1") (pin "2") (pinfunction "P$3_2") (pintype "power_in"))
      (node (ref "ZO1") (pin "4") (pinfunction "P$4_4") (pintype "power_in"))
    )
    (net (code "19") (name "IT_ACCEL_1") (class "Default")
      (node (ref "U8") (pin "11") (pinfunction "INT1_11") (pintype "bidirectional"))
    )
    (net (code "20") (name "NRST") (class "Default")
      (node (ref "C10") (pin "1") (pinfunction "P$1_1") (pintype "passive"))
      (node (ref "R23") (pin "1") (pinfunction "1_1") (pintype "passive"))
      (node (ref "S5") (pin "3") (pinfunction "3_3") (pintype "passive"))
      (node (ref "S5") (pin "4") (pinfunction "4_4") (pintype "passive"))
      (node (ref "U3") (pin "7") (pinfunction "NRST_7") (pintype "bidirectional"))
    )
    (net (code "21") (name "Net-(AMP1-OUT)") (class "Default")
      (node (ref "AMP1") (pin "1") (pinfunction "OUT_1") (pintype "output"))
      (node (ref "C34") (pin "1") (pinfunction "P$1_1") (pintype "passive"))
      (node (ref "R44") (pin "1") (pinfunction "1_1") (pintype "passive"))
      (node (ref "R45") (pin "2") (pinfunction "2_2") (pintype "passive"))
    )
    (net (code "22") (name "Net-(AMP1-V+)") (class "Default")
      (node (ref "AMP1") (pin "5") (pinfunction "V+_5") (pintype "power_in"))
      (node (ref "FB3") (pin "1") (pinfunction "1_1") (pintype "bidirectional"))
    )
    (net (code "23") (name "Net-(C1-P$1)") (class "Default")
      (node (ref "C1") (pin "1") (pinfunction "P$1_1") (pintype "passive"))
      (node (ref "DA1") (pin "10") (pinfunction "IN+_10") (pintype "bidirectional"))
      (node (ref "R36") (pin "1") (pinfunction "1_1") (pintype "passive"))
    )
    (net (code "24") (name "Net-(C1-P$2)") (class "Default")
      (node (ref "C1") (pin "2") (pinfunction "P$2_2") (pintype "passive"))
      (node (ref "DA1") (pin "9") (pinfunction "IN-_9") (pintype "bidirectional"))
      (node (ref "R37") (pin "1") (pinfunction "1_1") (pintype "passive"))
    )
    (net (code "25") (name "Net-(C3-P$1)") (class "Default")
      (node (ref "C3") (pin "1") (pinfunction "P$1_1") (pintype "passive"))
      (node (ref "R9") (pin "2") (pinfunction "2_2") (pintype "passive"))
      (node (ref "S1") (pin "3") (pinfunction "3_3") (pintype "passive"))
      (node (ref "S1") (pin "4") (pinfunction "4_4") (pintype "passive"))
    )
    (net (code "26") (name "Net-(C6-P$1)") (class "Default")
      (node (ref "C6") (pin "1") (pinfunction "P$1_1") (pintype "passive"))
      (node (ref "R14") (pin "2") (pinfunction "2_2") (pintype "passive"))
      (node (ref "S2") (pin "3") (pinfunction "3_3") (pintype "passive"))
      (node (ref "S2") (pin "4") (pinfunction "4_4") (pintype "passive"))
    )
    (net (code "27") (name "Net-(C11-P$2)") (class "Default")
      (node (ref "C11") (pin "2") (pinfunction "P$2_2") (pintype "passive"))
      (node (ref "FB2") (pin "1") (pinfunction "1_1") (pintype "bidirectional"))
      (node (ref "U3") (pin "9") (pinfunction "VREF+_9") (pintype "bidirectional"))
    )
    (net (code "28") (name "Net-(C16-P$2)") (class "Default")
      (node (ref "C16") (pin "2") (pinfunction "P$2_2") (pintype "passive"))
      (node (ref "Q4") (pin "3") (pinfunction "C_3") (pintype "passive"))
      (node (ref "R35") (pin "2") (pinfunction "2_2") (pintype "passive"))
    )
    (net (code "29") (name "Net-(C17-P$1)") (class "Default")
      (node (ref "C17") (pin "1") (pinfunction "P$1_1") (pintype "passive"))
      (node (ref "R11") (pin "2") (pinfunction "2_2") (pintype "passive"))
      (node (ref "R12") (pin "2") (pinfunction "2_2") (pintype "passive"))
    )
    (net (code "30") (name "Net-(C21-P$1)") (class "Default")
      (node (ref "C21") (pin "1") (pinfunction "P$1_1") (pintype "passive"))
      (node (ref "LCD1") (pin "1") (pinfunction "C2+_1") (pintype "bidirectional"))
    )
    (net (code "31") (name "Net-(C21-P$2)") (class "Default")
      (node (ref "C21") (pin "2") (pinfunction "P$2_2") (pintype "passive"))
      (node (ref "LCD1") (pin "2") (pinfunction "C2-_2") (pintype "bidirectional"))
    )
    (net (code "32") (name "Net-(C22-P$1)") (class "Default")
      (node (ref "C22") (pin "1") (pinfunction "P$1_1") (pintype "passive"))
      (node (ref "LCD1") (pin "3") (pinfunction "C1+_3") (pintype "bidirectional"))
    )
    (net (code "33") (name "Net-(C22-P$2)") (class "Default")
      (node (ref "C22") (pin "2") (pinfunction "P$2_2") (pintype "passive"))
      (node (ref "LCD1") (pin "4") (pinfunction "C1-_4") (pintype "bidirectional"))
    )
    (net (code "34") (name "Net-(C25-P$1)") (class "Default")
      (node (ref "C25") (pin "1") (pinfunction "P$1_1") (pintype "passive"))
      (node (ref "LCD1") (pin "13") (pinfunction "VCOMH_13") (pintype "power_in"))
    )
    (net (code "35") (name "Net-(C26-P$1)") (class "Default")
      (node (ref "C26") (pin "1") (pinfunction "P$1_1") (pintype "passive"))
      (node (ref "LCD1") (pin "14") (pinfunction "VCC_14") (pintype "power_in"))
    )
    (net (code "36") (name "Net-(C27-P$1)") (class "Default")
      (node (ref "C27") (pin "1") (pinfunction "P$1_1") (pintype "passive"))
      (node (ref "D9") (pin "C") (pinfunction "C_C") (pintype "passive"))
      (node (ref "PAD1") (pin "TP") (pinfunction "TP_TP") (pintype "input"))
      (node (ref "PAD2") (pin "TP") (pinfunction "TP_TP") (pintype "input"))
      (node (ref "PAD3") (pin "TP") (pinfunction "TP_TP") (pintype "input"))
      (node (ref "PAD4") (pin "TP") (pinfunction "TP_TP") (pintype "input"))
      (node (ref "Q3") (pin "5") (pinfunction "D_5") (pintype "passive"))
      (node (ref "Q3") (pin "6") (pinfunction "D_6") (pintype "passive"))
      (node (ref "Q3") (pin "7") (pinfunction "D_7") (pintype "passive"))
      (node (ref "Q3") (pin "8") (pinfunction "D_8") (pintype "passive"))
      (node (ref "Q3") (pin "9") (pinfunction "D_9") (pintype "passive"))
      (node (ref "R13") (pin "1") (pinfunction "1_1") (pintype "passive"))
      (node (ref "R42") (pin "2") (pinfunction "2_2") (pintype "passive"))
      (node (ref "T1") (pin "1A") (pinfunction "P$1_1A") (pintype "bidirectional"))
      (node (ref "T1") (pin "1B") (pinfunction "P$1_1B") (pintype "bidirectional"))
    )
    (net (code "37") (name "Net-(C29-P$1)") (class "Default")
      (node (ref "C29") (pin "1") (pinfunction "P$1_1") (pintype "passive"))
      (node (ref "U4") (pin "1") (pinfunction "BS_1") (pintype "bidirectional"))
    )
    (net (code "38") (name "Net-(C29-P$2)") (class "Default")
      (node (ref "C29") (pin "2") (pinfunction "P$2_2") (pintype "passive"))
      (node (ref "D7") (pin "C") (pinfunction "C_C") (pintype "passive"))
      (node (ref "L1") (pin "1") (pinfunction "1_1") (pintype "passive"))
      (node (ref "U4") (pin "6") (pinfunction "SW_6") (pintype "bidirectional"))
    )
    (net (code "39") (name "Net-(C32-P$1)") (class "Default")
      (node (ref "C32") (pin "1") (pinfunction "P$1_1") (pintype "passive"))
      (node (ref "U3") (pin "22") (pinfunction "VCAP1_22") (pintype "bidirectional"))
    )
    (net (code "40") (name "Net-(C35-P$2)") (class "Default")
      (node (ref "C35") (pin "2") (pinfunction "P$2_2") (pintype "passive"))
      (node (ref "R1") (pin "2") (pinfunction "2_2") (pintype "passive"))
      (node (ref "R2") (pin "2") (pinfunction "2_2") (pintype "passive"))
      (node (ref "U4") (pin "3") (pinfunction "FB_3") (pintype "bidirectional"))
    )
    (net (code "41") (name "Net-(D3-PadC)") (class "Default")
      (node (ref "D3") (pin "C") (pinfunction "C_C") (pintype "passive"))
      (node (ref "Q2") (pin "1") (pinfunction "S_1") (pintype "passive"))
      (node (ref "Q2") (pin "2") (pinfunction "S_2") (pintype "passive"))
      (node (ref "Q2") (pin "3") (pinfunction "S_3") (pintype "passive"))
      (node (ref "Q3") (pin "1") (pinfunction "S_1") (pintype "passive"))
      (node (ref "Q3") (pin "2") (pinfunction "S_2") (pintype "passive"))
      (node (ref "Q3") (pin "3") (pinfunction "S_3") (pintype "passive"))
    )
    (net (code "42") (name "Net-(LCD1-IREF)") (class "Default")
      (node (ref "LCD1") (pin "12") (pinfunction "IREF_12") (pintype "bidirectional"))
      (node (ref "R17") (pin "2") (pinfunction "2_2") (pintype "passive"))
    )
    (net (code "43") (name "Net-(Q2-G)") (class "Default")
      (node (ref "D3") (pin "A") (pinfunction "A_A") (pintype "passive"))
      (node (ref "Q2") (pin "4") (pinfunction "G_4") (pintype "passive"))
      (node (ref "Q3") (pin "4") (pinfunction "G_4") (pintype "passive"))
      (node (ref "R10") (pin "2") (pinfunction "2_2") (pintype "passive"))
      (node (ref "R35") (pin "1") (pinfunction "1_1") (pintype "passive"))
    )
    (net (code "44") (name "Net-(Q4-B)") (class "Default")
      (node (ref "Q4") (pin "1") (pinfunction "B_1") (pintype "passive"))
      (node (ref "R11") (pin "1") (pinfunction "1_1") (pintype "passive"))
    )
    (net (code "45") (name "Net-(R7-Pad2)") (class "Default")
      (node (ref "R7") (pin "2") (pinfunction "2_2") (pintype "passive"))
      (node (ref "S3") (pin "1") (pinfunction "1_1") (pintype "passive"))
      (node (ref "S3") (pin "2") (pinfunction "2_2") (pintype "passive"))
    )
    (net (code "46") (name "Net-(U1-VBUS)") (class "Default")
      (node (ref "FB5") (pin "1") (pinfunction "1_1") (pintype "bidirectional"))
      (node (ref "U1") (pin "2") (pinfunction "VBUS_2") (pintype "bidirectional"))
    )
    (net (code "47") (name "Net-(U3-PB2)") (class "Default")
      (node (ref "JP1") (pin "2") (pinfunction "2_2") (pintype "passive"))
      (node (ref "U3") (pin "20") (pinfunction "PB2_20") (pintype "bidirectional"))
    )
    (net (code "48") (name "Net-(U4-EN)") (class "Default")
      (node (ref "R20") (pin "1") (pinfunction "1_1") (pintype "passive"))
      (node (ref "U4") (pin "4") (pinfunction "EN_4") (pintype "bidirectional"))
    )
    (net (code "49") (name "Net-(U5-VOUT)") (class "Default")
      (node (ref "R41") (pin "2") (pinfunction "2_2") (pintype "passive"))
      (node (ref "U5") (pin "2") (pinfunction "VOUT_2") (pintype "input"))
    )
    (net (code "50") (name "Net-(VD1-P$4)") (class "Default")
      (node (ref "R27") (pin "1") (pinfunction "1_1") (pintype "passive"))
      (node (ref "R4") (pin "1") (pinfunction "1_1") (pintype "passive"))
      (node (ref "R5") (pin "1") (pinfunction "1_1") (pintype "passive"))
      (node (ref "VD1") (pin "4") (pinfunction "P$4_4") (pintype "bidirectional"))
    )
    (net (code "51") (name "Net-(VD1-P$6)") (class "Default")
      (node (ref "R28") (pin "1") (pinfunction "1_1") (pintype "passive"))
      (node (ref "R6") (pin "1") (pinfunction "1_1") (pintype "passive"))
      (node (ref "VD1") (pin "6") (pinfunction "P$6_6") (pintype "bidirectional"))
    )
    (net (code "52") (name "OSC_IN") (class "Default")
      (node (ref "C8") (pin "2") (pinfunction "P$2_2") (pintype "passive"))
      (node (ref "U3") (pin "5") (pinfunction "PF0/OSC_IN_5") (pintype "bidirectional"))
      (node (ref "ZO1") (pin "3") (pinfunction "P$2_3") (pintype "bidirectional"))
    )
    (net (code "53") (name "OSC_OUT") (class "Default")
      (node (ref "C9") (pin "2") (pinfunction "P$2_2") (pintype "passive"))
      (node (ref "U3") (pin "6") (pinfunction "PF1/OSC_OUT\\_6") (pintype "bidirectional"))
      (node (ref "ZO1") (pin "1") (pinfunction "P$1_1") (pintype "bidirectional"))
    )
    (net (code "54") (name "PA0") (class "Default")
      (node (ref "U3") (pin "10") (pinfunction "PA0_10") (pintype "bidirectional"))
    )
    (net (code "55") (name "PA1") (class "Default")
      (node (ref "U3") (pin "11") (pinfunction "PA1_11") (pintype "bidirectional"))
    )
    (net (code "56") (name "PA2{slash}ADC2") (class "Default")
      (node (ref "R41") (pin "1") (pinfunction "1_1") (pintype "passive"))
      (node (ref "U3") (pin "12") (pinfunction "PA2_12") (pintype "bidirectional"))
    )
    (net (code "57") (name "PA3{slash}T2C4") (class "Default")
      (node (ref "C17") (pin "2") (pinfunction "P$2_2") (pintype "passive"))
      (node (ref "U3") (pin "13") (pinfunction "PA3_13") (pintype "bidirectional"))
    )
    (net (code "58") (name "PA4") (class "Default")
      (node (ref "U3") (pin "14") (pinfunction "PA4_14") (pintype "bidirectional"))
    )
    (net (code "59") (name "PA5") (class "Default")
      (node (ref "U3") (pin "15") (pinfunction "PA5_15") (pintype "bidirectional"))
    )
    (net (code "60") (name "PA6") (class "Default")
      (node (ref "U3") (pin "16") (pinfunction "PA6_16") (pintype "bidirectional"))
    )
    (net (code "61") (name "PA7{slash}T1CH1N{slash}T3C2") (class "Default")
      (node (ref "BUZ1") (pin "+") (pinfunction "LEAD+_+") (pintype "passive"))
      (node (ref "U3") (pin "17") (pinfunction "PA7_17") (pintype "bidirectional"))
    )
    (net (code "62") (name "PA8{slash}SCL3") (class "Default")
      (node (ref "DA1") (pin "5") (pinfunction "SCL_5") (pintype "bidirectional"))
      (node (ref "R3") (pin "2") (pinfunction "2_2") (pintype "passive"))
      (node (ref "U1") (pin "6") (pinfunction "SCL_6") (pintype "bidirectional"))
      (node (ref "U3") (pin "29") (pinfunction "PA8_29") (pintype "bidirectional"))
      (node (ref "U8") (pin "4") (pinfunction "SCL/SPC_4") (pintype "bidirectional"))
    )
    (net (code "63") (name "PA9{slash}T1C2") (class "Default")
      (node (ref "U3") (pin "30") (pinfunction "PA9_30") (pintype "bidirectional"))
    )
    (net (code "64") (name "PA10{slash}IT_ACCEL_2") (class "Default")
      (node (ref "U3") (pin "31") (pinfunction "PA10_31") (pintype "bidirectional"))
      (node (ref "U8") (pin "9") (pinfunction "INT2_9") (pintype "bidirectional"))
    )
    (net (code "65") (name "PA11{slash}USB_DM") (class "Default")
      (node (ref "R6") (pin "2") (pinfunction "2_2") (pintype "passive"))
      (node (ref "U3") (pin "32") (pinfunction "PA11_32") (pintype "bidirectional"))
    )
    (net (code "66") (name "PA12{slash}USB_DP") (class "Default")
      (node (ref "R5") (pin "2") (pinfunction "2_2") (pintype "passive"))
      (node (ref "U3") (pin "33") (pinfunction "PA12_33") (pintype "bidirectional"))
    )
    (net (code "67") (name "PA13{slash}SWDIO") (class "Default")
      (node (ref "R27") (pin "2") (pinfunction "2_2") (pintype "passive"))
      (node (ref "U3") (pin "34") (pinfunction "PA13_34") (pintype "bidirectional"))
    )
    (net (code "68") (name "PA14{slash}SWCLK") (class "Default")
      (node (ref "R28") (pin "2") (pinfunction "2_2") (pintype "passive"))
      (node (ref "U3") (pin "37") (pinfunction "PA14_37") (pintype "bidirectional"))
    )
    (net (code "69") (name "PA15") (class "Default")
      (node (ref "U3") (pin "38") (pinfunction "PA15_38") (pintype "bidirectional"))
    )
    (net (code "70") (name "PB0{slash}ADC8") (class "Default")
      (node (ref "R45") (pin "1") (pinfunction "1_1") (pintype "passive"))
      (node (ref "U3") (pin "18") (pinfunction "PB0_18") (pintype "bidirectional"))
    )
    (net (code "71") (name "PB1{slash}IT_FUSB302") (class "Default")
      (node (ref "R16") (pin "2") (pinfunction "2_2") (pintype "passive"))
      (node (ref "U1") (pin "5") (pinfunction "~{INT}_5") (pintype "bidirectional"))
      (node (ref "U3") (pin "19") (pinfunction "PB1_19") (pintype "bidirectional"))
    )
    (net (code "72") (name "PB3") (class "Default")
      (node (ref "U3") (pin "39") (pinfunction "PB3_39") (pintype "bidirectional"))
    )
    (net (code "73") (name "PB4{slash}SDA3") (class "Default")
      (node (ref "DA1") (pin "4") (pinfunction "SDA_4") (pintype "bidirectional"))
      (node (ref "R25") (pin "2") (pinfunction "2_2") (pintype "passive"))
      (node (ref "U1") (pin "7") (pinfunction "SDA_7") (pintype "bidirectional"))
      (node (ref "U3") (pin "40") (pinfunction "PB4_40") (pintype "bidirectional"))
      (node (ref "U8") (pin "6") (pinfunction "SDA/SDI_6") (pintype "bidirectional"))
    )
    (net (code "74") (name "PB5") (class "Default")
      (node (ref "U3") (pin "41") (pinfunction "PB5_41") (pintype "bidirectional"))
    )
    (net (code "75") (name "PB6{slash}SCL1") (class "Default")
      (node (ref "LCD1") (pin "10") (pinfunction "SCL_10") (pintype "bidirectional"))
      (node (ref "R19") (pin "1") (pinfunction "1_1") (pintype "passive"))
      (node (ref "U3") (pin "42") (pinfunction "PB6_42") (pintype "bidirectional"))
    )
    (net (code "76") (name "PB7{slash}SDA1") (class "Default")
      (node (ref "LCD1") (pin "11") (pinfunction "SDA_11") (pintype "bidirectional"))
      (node (ref "R18") (pin "1") (pinfunction "1_1") (pintype "passive"))
      (node (ref "U3") (pin "43") (pinfunction "PB7_43") (pintype "bidirectional"))
    )
    (net (code "77") (name "PB8&BOOT0_S3") (class "Default")
      (node (ref "R7") (pin "1") (pinfunction "1_1") (pintype "passive"))
      (node (ref "R8") (pin "1") (pinfunction "1_1") (pintype "passive"))
      (node (ref "U3") (pin "44") (pinfunction "BOOT0_44") (pintype "bidirectional"))
      (node (ref "U3") (pin "45") (pinfunction "PB8_45") (pintype "bidirectional"))
    )
    (net (code "78") (name "PB9{slash}S1") (class "Default")
      (node (ref "R9") (pin "1") (pinfunction "1_1") (pintype "passive"))
      (node (ref "U3") (pin "46") (pinfunction "PB9_46") (pintype "bidirectional"))
    )
    (net (code "79") (name "PB10") (class "Default")
      (node (ref "U3") (pin "21") (pinfunction "PB10_21") (pintype "bidirectional"))
    )
    (net (code "80") (name "PB12") (class "Default")
      (node (ref "U3") (pin "25") (pinfunction "PB12_25") (pintype "bidirectional"))
    )
    (net (code "81") (name "PB13{slash}IT_INA226") (class "Default")
      (node (ref "DA1") (pin "3") (pinfunction "ALERT_3") (pintype "bidirectional"))
      (node (ref "R38") (pin "2") (pinfunction "2_2") (pintype "passive"))
      (node (ref "U3") (pin "26") (pinfunction "PB13_26") (pintype "bidirectional"))
    )
    (net (code "82") (name "PB14{slash}MISO2") (class "Default")
      (node (ref "U3") (pin "27") (pinfunction "PB14_27") (pintype "bidirectional"))
    )
    (net (code "83") (name "PB15{slash}S2") (class "Default")
      (node (ref "R14") (pin "1") (pinfunction "1_1") (pintype "passive"))
      (node (ref "U3") (pin "28") (pinfunction "PB15_28") (pintype "bidirectional"))
    )
    (net (code "84") (name "PC13") (class "Default")
      (node (ref "U3") (pin "2") (pinfunction "PC13_2") (pintype "bidirectional"))
    )
    (net (code "85") (name "PC14{slash}OSC32_IN") (class "Default")
      (node (ref "U3") (pin "3") (pinfunction "PC14/OSC32_IN_3") (pintype "bidirectional"))
    )
    (net (code "86") (name "PC15{slash}OSC32_OUT") (class "Default")
      (node (ref "U3") (pin "4") (pinfunction "PC15/OSC32_OUT_4") (pintype "bidirectional"))
    )
    (net (code "87") (name "PGND") (class "Default")
      (node (ref "CP1") (pin "1A") (pinfunction "P$1_1A") (pintype "bidirectional"))
      (node (ref "CP1") (pin "1B") (pinfunction "P$1_1B") (pintype "bidirectional"))
      (node (ref "PAD10") (pin "TP") (pinfunction "TP_TP") (pintype "input"))
      (node (ref "PAD11") (pin "TP") (pinfunction "TP_TP") (pintype "input"))
      (node (ref "PAD12") (pin "TP") (pinfunction "TP_TP") (pintype "input"))
      (node (ref "PAD9") (pin "TP") (pinfunction "TP_TP") (pintype "input"))
      (node (ref "TP1") (pin "P$1") (pinfunction "P$1_P$1") (pintype "bidirectional"))
    )
    (net (code "88") (name "SAO{slash}SDO{slash}ADDR") (class "Default")
      (node (ref "U8") (pin "7") (pinfunction "SA0/SDO_7") (pintype "bidirectional"))
    )
    (net (code "89") (name "VBUS-C") (class "Default")
      (node (ref "D1") (pin "A") (pinfunction "A_A") (pintype "passive"))
      (node (ref "FB5") (pin "2") (pinfunction "2_2") (pintype "bidirectional"))
      (node (ref "Q2") (pin "5") (pinfunction "D_5") (pintype "passive"))
      (node (ref "Q2") (pin "6") (pinfunction "D_6") (pintype "passive"))
      (node (ref "Q2") (pin "7") (pinfunction "D_7") (pintype "passive"))
      (node (ref "Q2") (pin "8") (pinfunction "D_8") (pintype "passive"))
      (node (ref "Q2") (pin "9") (pinfunction "D_9") (pintype "passive"))
      (node (ref "R10") (pin "1") (pinfunction "1_1") (pintype "passive"))
      (node (ref "R24") (pin "1") (pinfunction "1_1") (pintype "passive"))
      (node (ref "R37") (pin "2") (pinfunction "2_2") (pintype "passive"))
    )
    (net (code "90") (name "unconnected-(J3-SBU1-PadA8)") (class "Default")
      (node (ref "J3") (pin "A8") (pinfunction "SBU1_A8") (pintype "bidirectional"))
    )
    (net (code "91") (name "unconnected-(J3-SBU2-PadB8)") (class "Default")
      (node (ref "J3") (pin "B8") (pinfunction "SBU2_B8") (pintype "bidirectional"))
    )
    (net (code "92") (name "unconnected-(U1-VCONN_01-Pad12)") (class "Default")
      (node (ref "U1") (pin "12") (pinfunction "VCONN_01_12") (pintype "bidirectional"))
    )
    (net (code "93") (name "unconnected-(U1-VCONN_02-Pad13)") (class "Default")
      (node (ref "U1") (pin "13") (pinfunction "VCONN_02_13") (pintype "bidirectional"))
    )
    (net (code "94") (name "unconnected-(VD1-P$5-Pad5)") (class "Default")
      (node (ref "VD1") (pin "5") (pinfunction "P$5_5") (pintype "bidirectional"))
    )
  )
)
